# PCB0M8B3.net
KiCad netlist of a schematic drawn in EAGLE
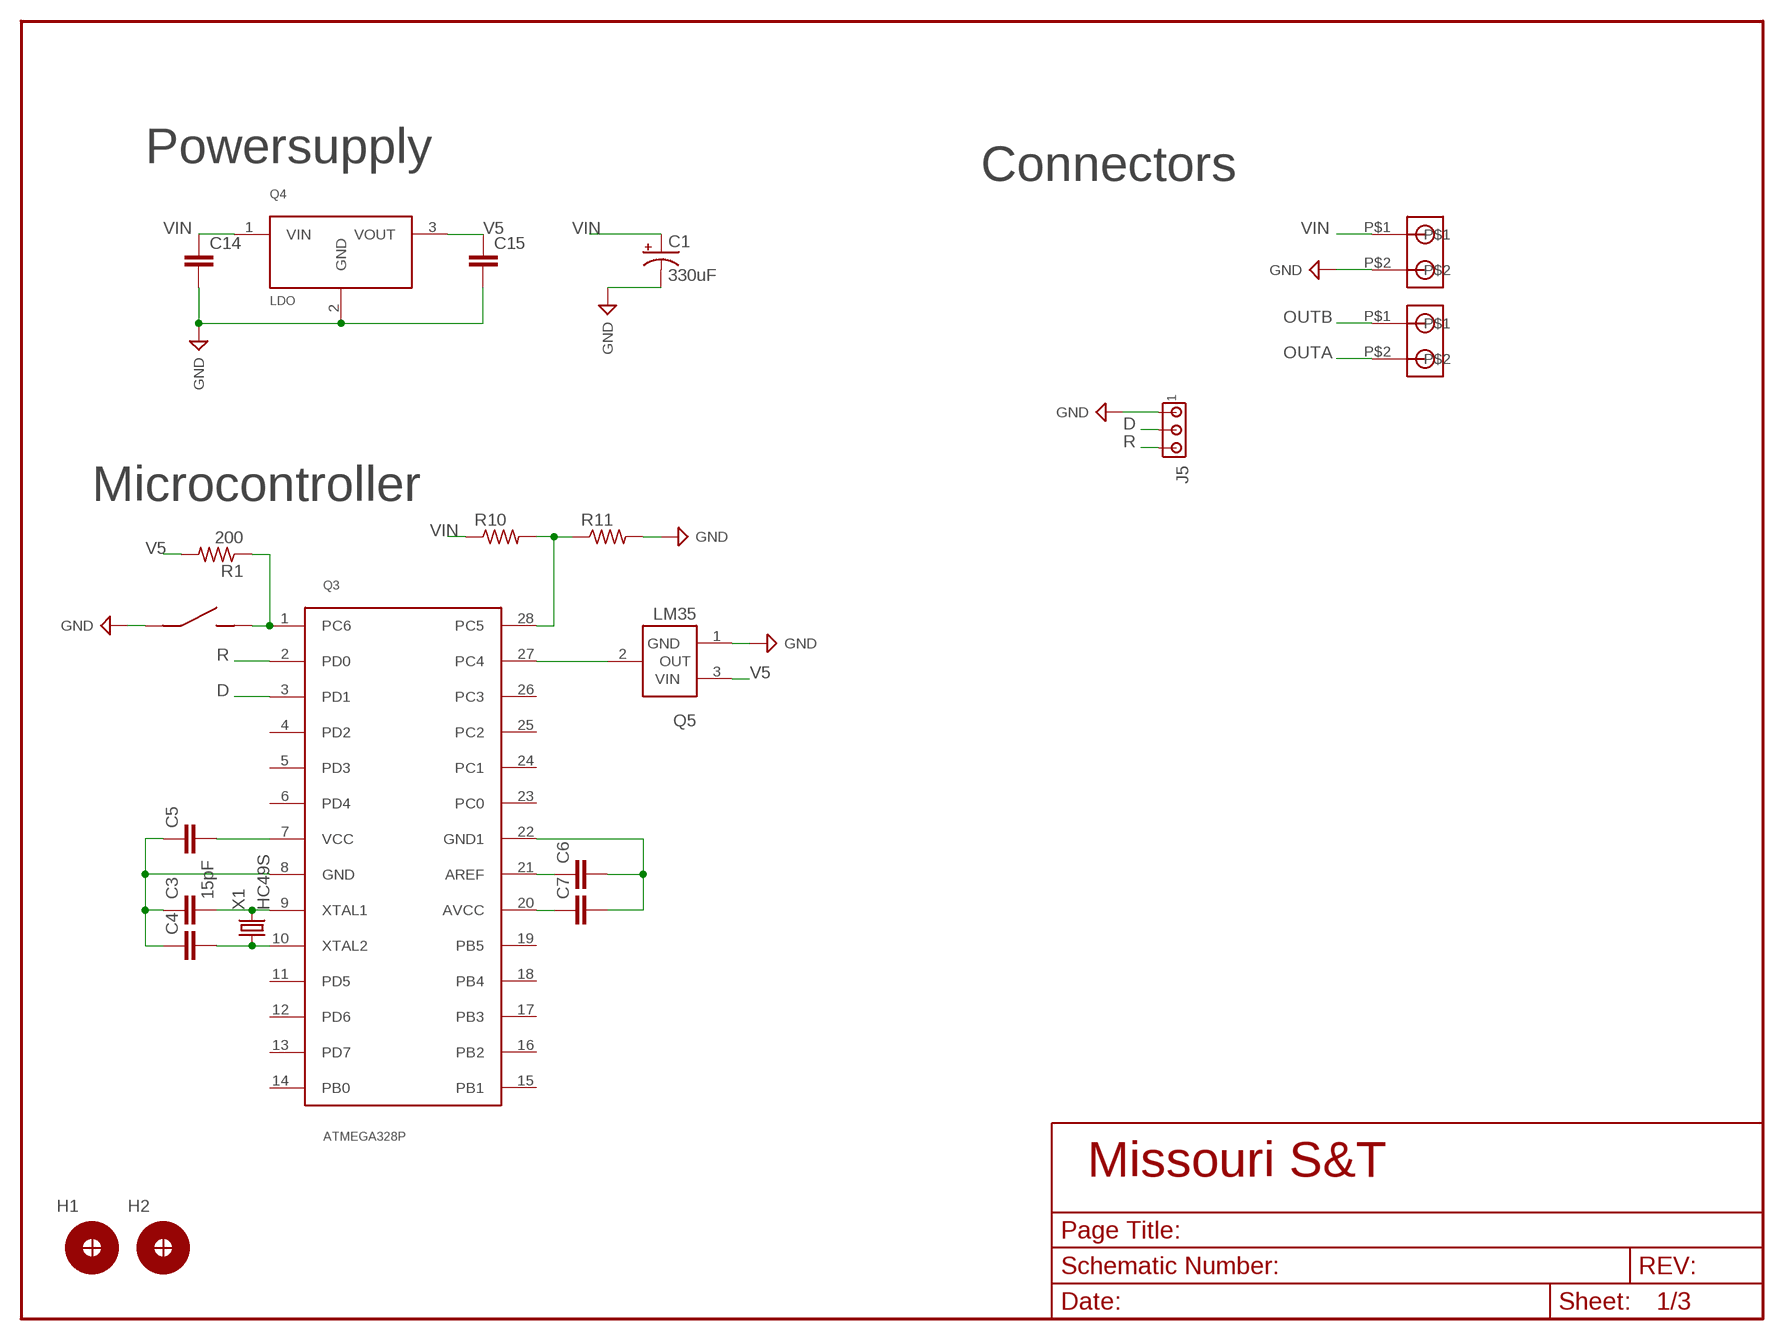
[diagram p0: schematic, sheet 1]
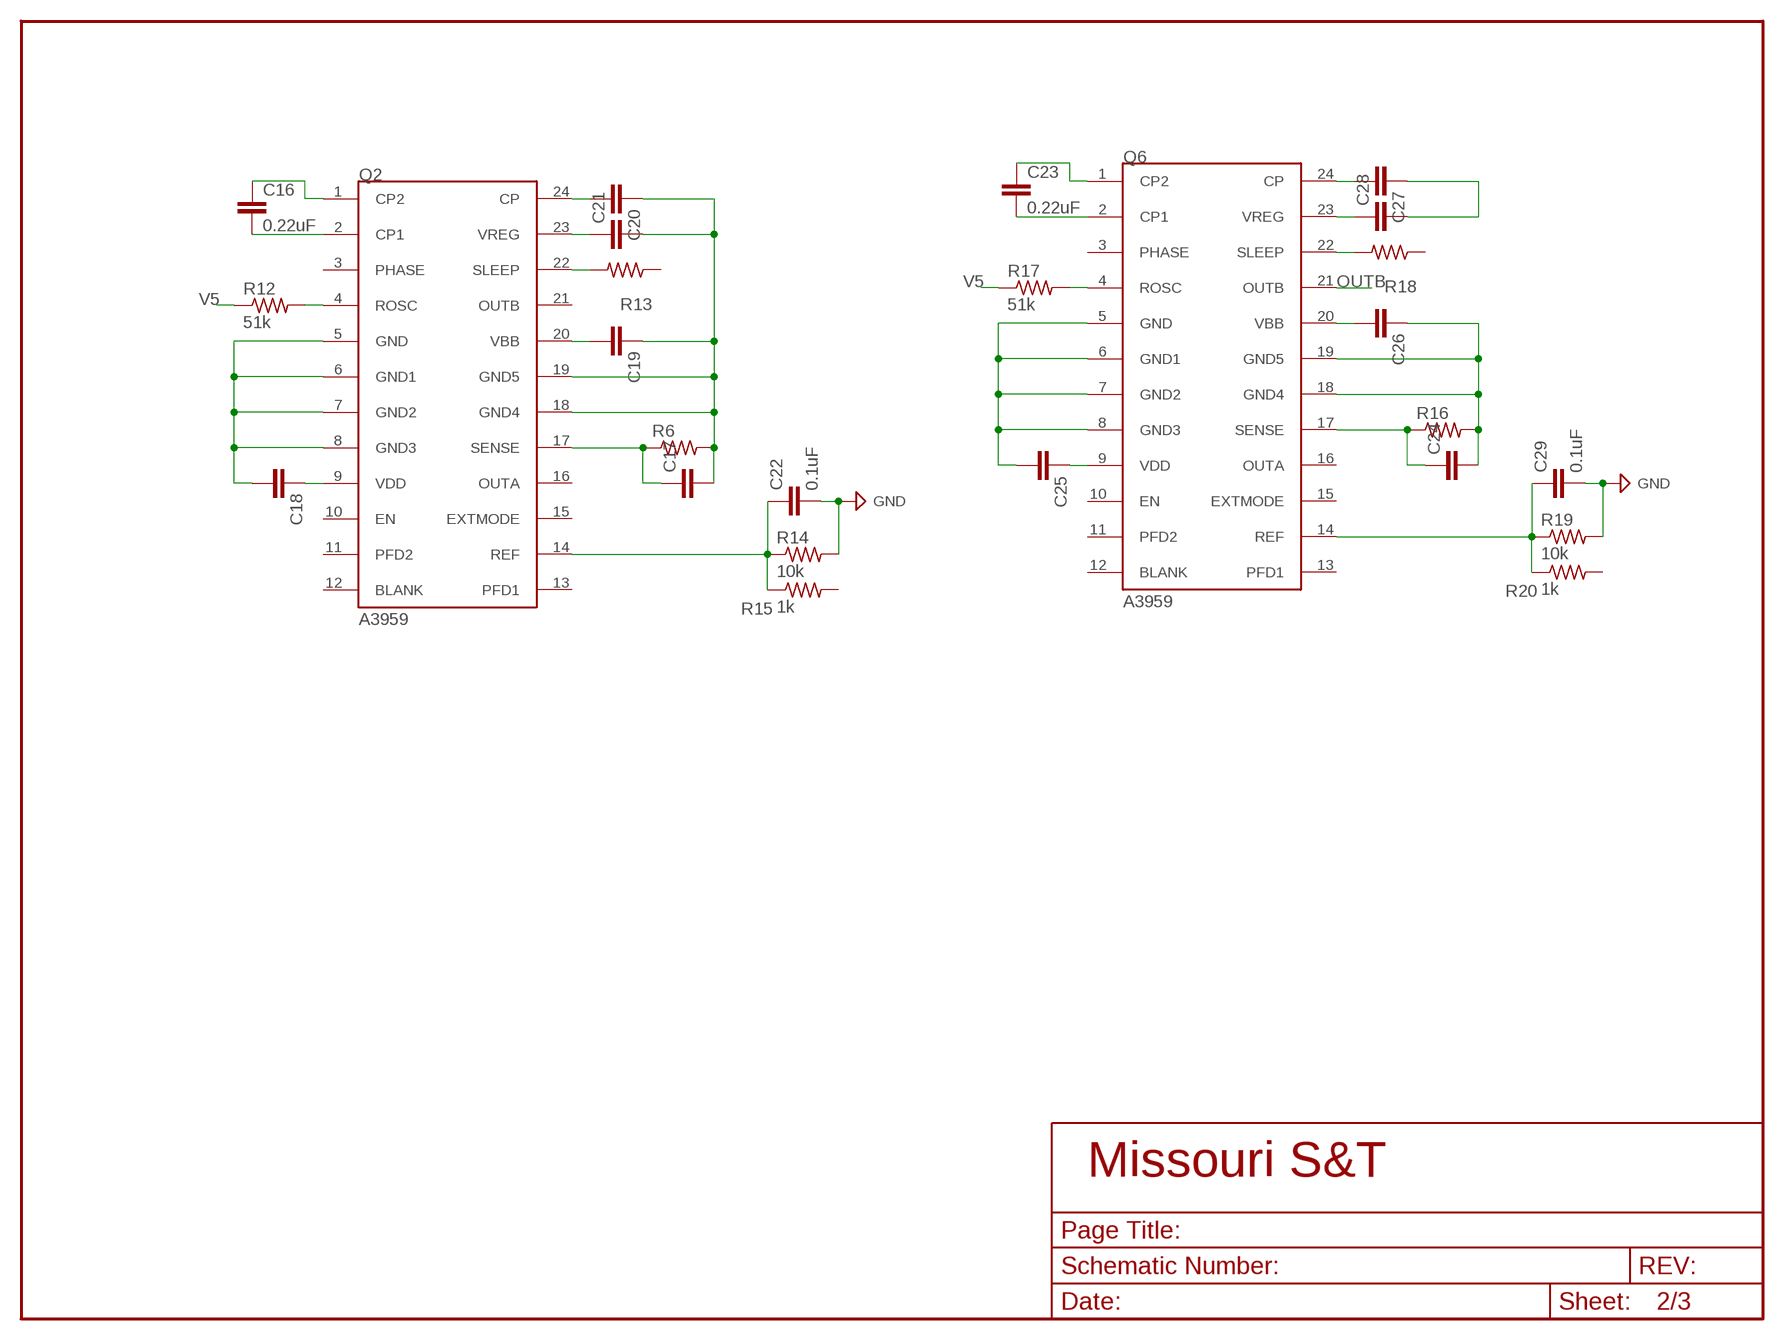
[diagram p1: schematic, sheet 2]
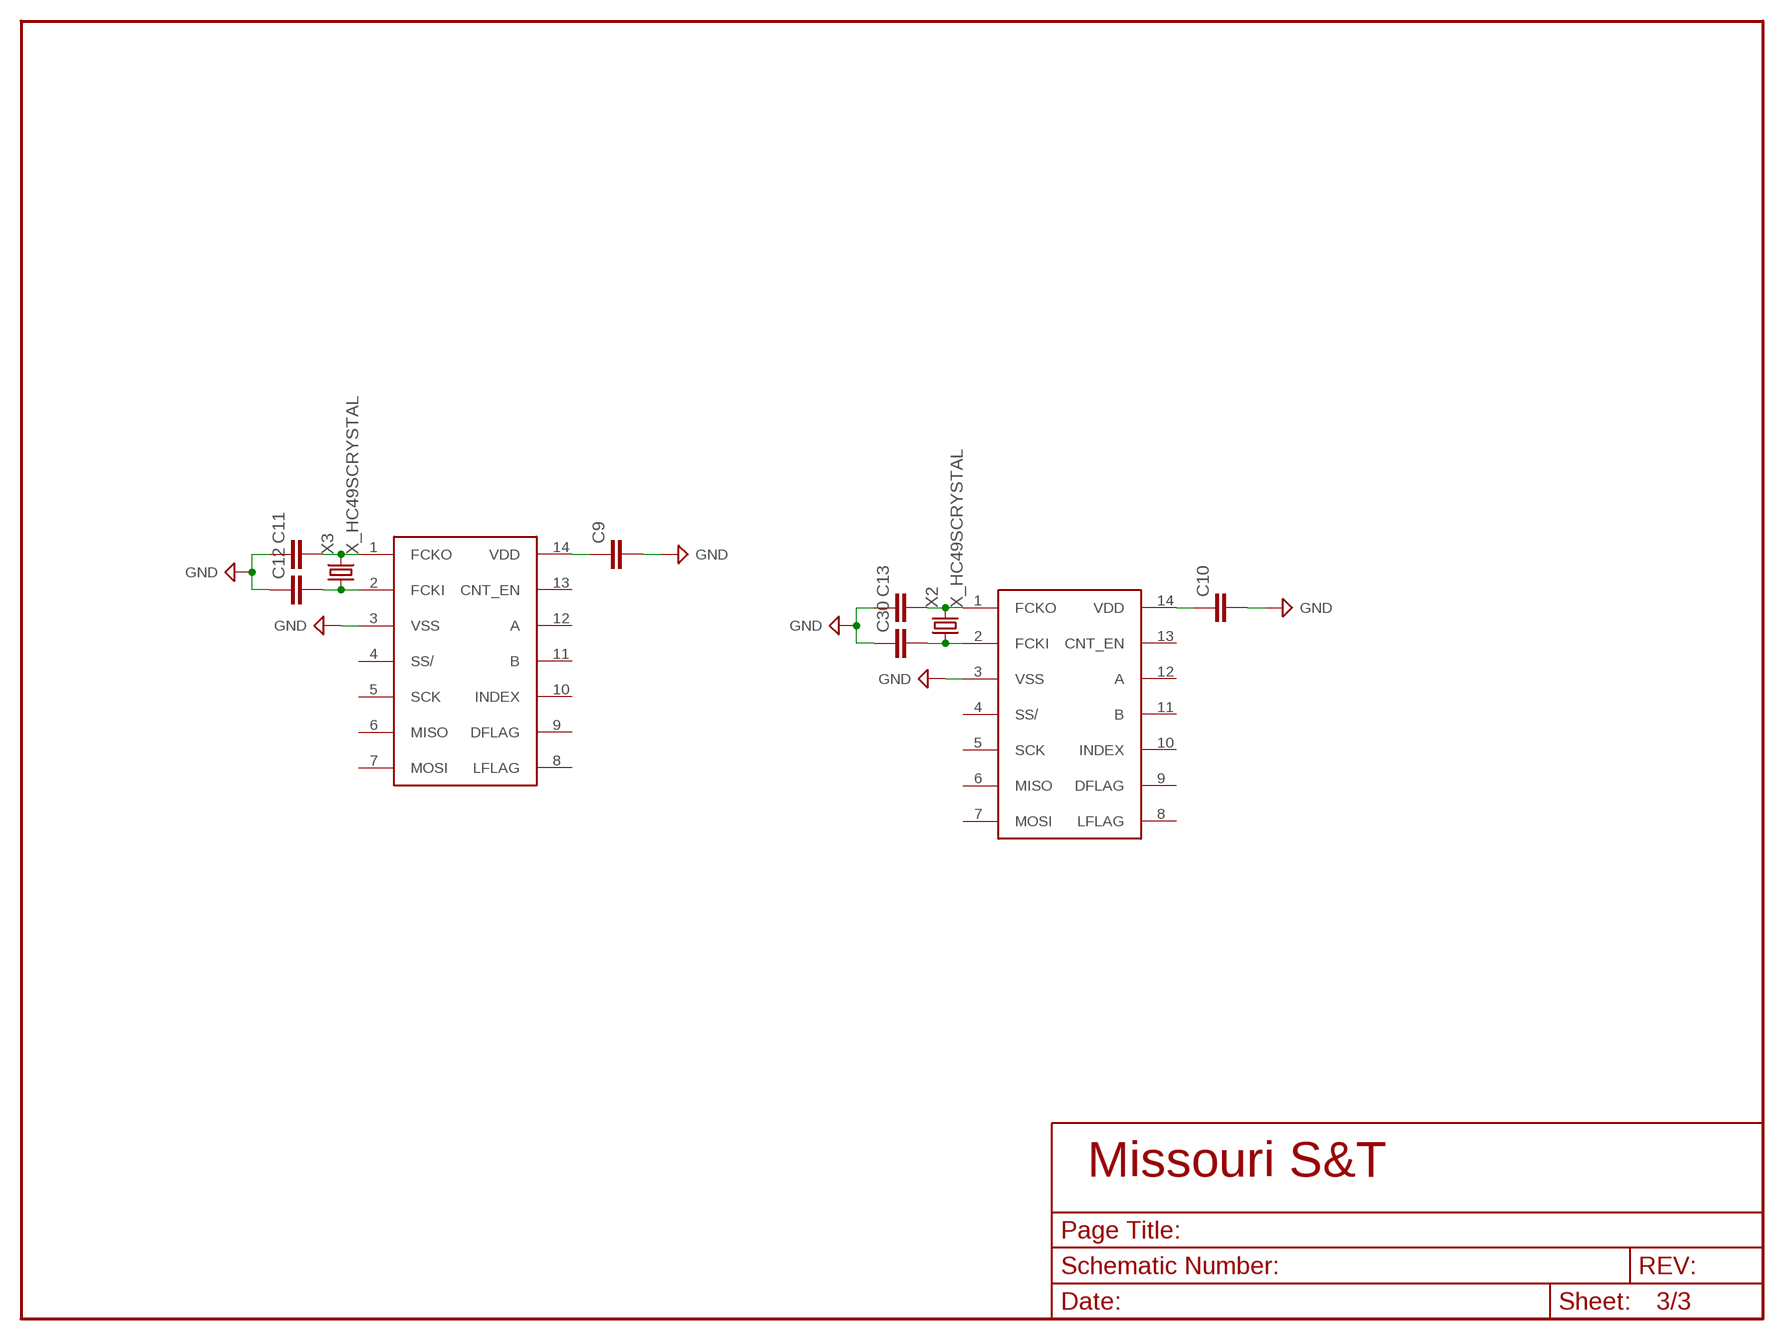
[diagram p2: schematic, sheet 3]

(export (version "E")
  (design (tool "Eeschema 10.0.6"))
  (components
    (comp (ref "C9")
      (value "C_CAP_1206")
      (footprint "eagle-import:C_1206")
      (libsource (lib "eagle-import") (part "C_CAP_1206"))
    )
    (comp (ref "C10")
      (value "C_CAP_0805")
      (footprint "eagle-import:C_0805")
      (libsource (lib "eagle-import") (part "C_CAP_0805"))
    )
    (comp (ref "C11")
      (value "C_CAP_0805")
      (footprint "eagle-import:C_0805")
      (libsource (lib "eagle-import") (part "C_CAP_0805"))
    )
    (comp (ref "C12")
      (value "C_CAP_0805")
      (footprint "eagle-import:C_0805")
      (libsource (lib "eagle-import") (part "C_CAP_0805"))
    )
    (comp (ref "C13")
      (value "C_CAP_0805")
      (footprint "eagle-import:C_0805")
      (libsource (lib "eagle-import") (part "C_CAP_0805"))
    )
    (comp (ref "C30")
      (value "C_CAP_0805")
      (footprint "eagle-import:C_0805")
      (libsource (lib "eagle-import") (part "C_CAP_0805"))
    )
    (comp (ref "Q8")
      (value "Q_LFLS7366R-S")
      (footprint "eagle-import:SOIC14")
      (libsource (lib "eagle-import") (part "Q_LFLS7366R-S"))
    )
    (comp (ref "Q9")
      (value "Q_LFLS7366R-S")
      (footprint "eagle-import:SOIC14")
      (libsource (lib "eagle-import") (part "Q_LFLS7366R-S"))
    )
    (comp (ref "X2")
      (value "X_HC49SCRYSTAL")
      (footprint "eagle-import:HC-49")
      (libsource (lib "eagle-import") (part "X_HC49SCRYSTAL"))
    )
    (comp (ref "X3")
      (value "X_HC49SCRYSTAL")
      (footprint "eagle-import:HC-49")
      (libsource (lib "eagle-import") (part "X_HC49SCRYSTAL"))
    )
    (comp (ref "C1")
      (value "330uF")
      (footprint "eagle-import:C_8MM")
      (libsource (lib "eagle-import") (part "C_POL8MM"))
    )
    (comp (ref "C3")
      (value "15pF")
      (footprint "eagle-import:C_0805")
      (libsource (lib "eagle-import") (part "C_CAP_0805"))
    )
    (comp (ref "C4")
      (value "C_CAP_0805")
      (footprint "eagle-import:C_0805")
      (libsource (lib "eagle-import") (part "C_CAP_0805"))
    )
    (comp (ref "C5")
      (value "C_CAP_0805")
      (footprint "eagle-import:C_0805")
      (libsource (lib "eagle-import") (part "C_CAP_0805"))
    )
    (comp (ref "C6")
      (value "C_CAP_0805")
      (footprint "eagle-import:C_0805")
      (libsource (lib "eagle-import") (part "C_CAP_0805"))
    )
    (comp (ref "C7")
      (value "C_CAP_0805")
      (footprint "eagle-import:C_0805")
      (libsource (lib "eagle-import") (part "C_CAP_0805"))
    )
    (comp (ref "C14")
      (value "C_CAP_0805")
      (footprint "eagle-import:C_0805")
      (libsource (lib "eagle-import") (part "C_CAP_0805"))
    )
    (comp (ref "C15")
      (value "C_CAP_0805")
      (footprint "eagle-import:C_0805")
      (libsource (lib "eagle-import") (part "C_CAP_0805"))
    )
    (comp (ref "H1")
      (value "H_MNTHOLE_#4")
      (footprint "eagle-import:H_MNTHOLE_#4")
      (libsource (lib "eagle-import") (part "H_MNTHOLE_#4"))
    )
    (comp (ref "H2")
      (value "H_MNTHOLE_#4")
      (footprint "eagle-import:H_MNTHOLE_#4")
      (libsource (lib "eagle-import") (part "H_MNTHOLE_#4"))
    )
    (comp (ref "J1")
      (value "J_1546074-2282834-2")
      (footprint "eagle-import:J_2.54MM")
      (libsource (lib "eagle-import") (part "J_1546074-2282834-2"))
    )
    (comp (ref "J2")
      (value "J_1546074-2282834-2")
      (footprint "eagle-import:J_2.54MM")
      (libsource (lib "eagle-import") (part "J_1546074-2282834-2"))
    )
    (comp (ref "J4")
      (value "J_MC32857")
      (footprint "eagle-import:J_TOGGLE")
      (libsource (lib "eagle-import") (part "J_MC32857"))
    )
    (comp (ref "J5")
      (value "J_MTA3P_100")
      (footprint "eagle-import:J_MTA100_3P")
      (libsource (lib "eagle-import") (part "J_MTA3P_100"))
    )
    (comp (ref "Q3")
      (value "ATMEGA328P")
      (footprint "eagle-import:DIP28")
      (libsource (lib "eagle-import") (part "Q_ATMEGA328P"))
    )
    (comp (ref "Q4")
      (value "LDO")
      (footprint "eagle-import:TO-220")
      (libsource (lib "eagle-import") (part "Q_LDO"))
    )
    (comp (ref "Q5")
      (value "LM35")
      (footprint "eagle-import:TO-92-3")
      (libsource (lib "eagle-import") (part "Q_LM35"))
    )
    (comp (ref "R1")
      (value "200")
      (footprint "eagle-import:R_0805")
      (libsource (lib "eagle-import") (part "R_RES_0805"))
    )
    (comp (ref "R10")
      (value "R_RES_0805")
      (footprint "eagle-import:R_0805")
      (libsource (lib "eagle-import") (part "R_RES_0805"))
    )
    (comp (ref "R11")
      (value "R_RES_0805")
      (footprint "eagle-import:R_0805")
      (libsource (lib "eagle-import") (part "R_RES_0805"))
    )
    (comp (ref "X1")
      (value "HC49S")
      (footprint "eagle-import:HC-49")
      (libsource (lib "eagle-import") (part "X_HC49SCRYSTAL"))
    )
    (comp (ref "C16")
      (value "0.22uF")
      (footprint "eagle-import:C_0805")
      (libsource (lib "eagle-import") (part "C_CAP_0805"))
    )
    (comp (ref "C17")
      (value "C_CAP_0805")
      (footprint "eagle-import:C_0805")
      (libsource (lib "eagle-import") (part "C_CAP_0805"))
    )
    (comp (ref "C18")
      (value "C_CAP_0805")
      (footprint "eagle-import:C_0805")
      (libsource (lib "eagle-import") (part "C_CAP_0805"))
    )
    (comp (ref "C19")
      (value "C_CAP_0805")
      (footprint "eagle-import:C_0805")
      (libsource (lib "eagle-import") (part "C_CAP_0805"))
    )
    (comp (ref "C20")
      (value "C_CAP_0805")
      (footprint "eagle-import:C_0805")
      (libsource (lib "eagle-import") (part "C_CAP_0805"))
    )
    (comp (ref "C21")
      (value "C_CAP_0805")
      (footprint "eagle-import:C_0805")
      (libsource (lib "eagle-import") (part "C_CAP_0805"))
    )
    (comp (ref "C22")
      (value "0.1uF")
      (footprint "eagle-import:C_0805")
      (libsource (lib "eagle-import") (part "C_CAP_0805"))
    )
    (comp (ref "C23")
      (value "0.22uF")
      (footprint "eagle-import:C_0805")
      (libsource (lib "eagle-import") (part "C_CAP_0805"))
    )
    (comp (ref "C24")
      (value "C_CAP_0805")
      (footprint "eagle-import:C_0805")
      (libsource (lib "eagle-import") (part "C_CAP_0805"))
    )
    (comp (ref "C25")
      (value "C_CAP_0805")
      (footprint "eagle-import:C_0805")
      (libsource (lib "eagle-import") (part "C_CAP_0805"))
    )
    (comp (ref "C26")
      (value "C_CAP_0805")
      (footprint "eagle-import:C_0805")
      (libsource (lib "eagle-import") (part "C_CAP_0805"))
    )
    (comp (ref "C27")
      (value "C_CAP_0805")
      (footprint "eagle-import:C_0805")
      (libsource (lib "eagle-import") (part "C_CAP_0805"))
    )
    (comp (ref "C28")
      (value "C_CAP_0805")
      (footprint "eagle-import:C_0805")
      (libsource (lib "eagle-import") (part "C_CAP_0805"))
    )
    (comp (ref "C29")
      (value "0.1uF")
      (footprint "eagle-import:C_0805")
      (libsource (lib "eagle-import") (part "C_CAP_0805"))
    )
    (comp (ref "Q2")
      (value "A3959")
      (footprint "eagle-import:DIP24")
      (libsource (lib "eagle-import") (part "Q_A3959"))
    )
    (comp (ref "Q6")
      (value "A3959")
      (footprint "eagle-import:DIP24")
      (libsource (lib "eagle-import") (part "Q_A3959"))
    )
    (comp (ref "R6")
      (value "R_RES_2010")
      (footprint "eagle-import:R_2010")
      (libsource (lib "eagle-import") (part "R_RES_2010"))
    )
    (comp (ref "R12")
      (value "51k")
      (footprint "eagle-import:R_0805")
      (libsource (lib "eagle-import") (part "R_RES_0805"))
    )
    (comp (ref "R13")
      (value "R_1/4WL")
      (footprint "eagle-import:R_1_4WL")
      (libsource (lib "eagle-import") (part "R_1/4WL"))
    )
    (comp (ref "R14")
      (value "10k")
      (footprint "eagle-import:R_0805")
      (libsource (lib "eagle-import") (part "R_RES_0805"))
    )
    (comp (ref "R15")
      (value "1k")
      (footprint "eagle-import:R_0805")
      (libsource (lib "eagle-import") (part "R_RES_0805"))
    )
    (comp (ref "R16")
      (value "R_RES_2010")
      (footprint "eagle-import:R_2010")
      (libsource (lib "eagle-import") (part "R_RES_2010"))
    )
    (comp (ref "R17")
      (value "51k")
      (footprint "eagle-import:R_0805")
      (libsource (lib "eagle-import") (part "R_RES_0805"))
    )
    (comp (ref "R18")
      (value "R_1/4WL")
      (footprint "eagle-import:R_1_4WL")
      (libsource (lib "eagle-import") (part "R_1/4WL"))
    )
    (comp (ref "R19")
      (value "10k")
      (footprint "eagle-import:R_0805")
      (libsource (lib "eagle-import") (part "R_RES_0805"))
    )
    (comp (ref "R20")
      (value "1k")
      (footprint "eagle-import:R_0805")
      (libsource (lib "eagle-import") (part "R_RES_0805"))
    )
  )
  (nets
    (net (code "1") (name "D") (class "Default")
      (node (ref "J5") (pin "2") (pinfunction "2_2") (pintype "passive"))
      (node (ref "Q3") (pin "3") (pinfunction "PD1_3") (pintype "bidirectional"))
    )
    (net (code "2") (name "GND") (class "Default")
      (node (ref "C1") (pin "-") (pinfunction "-_-") (pintype "passive"))
      (node (ref "C10") (pin "2") (pinfunction "2_2") (pintype "passive"))
      (node (ref "C11") (pin "1") (pinfunction "1_1") (pintype "passive"))
      (node (ref "C12") (pin "1") (pinfunction "1_1") (pintype "passive"))
      (node (ref "C13") (pin "1") (pinfunction "1_1") (pintype "passive"))
      (node (ref "C14") (pin "2") (pinfunction "2_2") (pintype "passive"))
      (node (ref "C15") (pin "2") (pinfunction "2_2") (pintype "passive"))
      (node (ref "C17") (pin "2") (pinfunction "2_2") (pintype "passive"))
      (node (ref "C18") (pin "2") (pinfunction "2_2") (pintype "passive"))
      (node (ref "C19") (pin "1") (pinfunction "1_1") (pintype "passive"))
      (node (ref "C20") (pin "1") (pinfunction "1_1") (pintype "passive"))
      (node (ref "C21") (pin "2") (pinfunction "2_2") (pintype "passive"))
      (node (ref "C22") (pin "2") (pinfunction "2_2") (pintype "passive"))
      (node (ref "C24") (pin "2") (pinfunction "2_2") (pintype "passive"))
      (node (ref "C25") (pin "2") (pinfunction "2_2") (pintype "passive"))
      (node (ref "C26") (pin "1") (pinfunction "1_1") (pintype "passive"))
      (node (ref "C29") (pin "2") (pinfunction "2_2") (pintype "passive"))
      (node (ref "C3") (pin "1") (pinfunction "1_1") (pintype "passive"))
      (node (ref "C30") (pin "1") (pinfunction "1_1") (pintype "passive"))
      (node (ref "C4") (pin "1") (pinfunction "1_1") (pintype "passive"))
      (node (ref "C5") (pin "1") (pinfunction "1_1") (pintype "passive"))
      (node (ref "C6") (pin "2") (pinfunction "2_2") (pintype "passive"))
      (node (ref "C7") (pin "2") (pinfunction "2_2") (pintype "passive"))
      (node (ref "C9") (pin "2") (pinfunction "2_2") (pintype "passive"))
      (node (ref "J1") (pin "P$2") (pinfunction "P$2_P$2") (pintype "bidirectional"))
      (node (ref "J4") (pin "P$1") (pinfunction "1_P$1") (pintype "bidirectional"))
      (node (ref "J5") (pin "1") (pinfunction "1_1") (pintype "passive"))
      (node (ref "Q2") (pin "18") (pinfunction "GND4_18") (pintype "bidirectional"))
      (node (ref "Q2") (pin "19") (pinfunction "GND5_19") (pintype "bidirectional"))
      (node (ref "Q2") (pin "5") (pinfunction "GND_5") (pintype "bidirectional"))
      (node (ref "Q2") (pin "6") (pinfunction "GND1_6") (pintype "bidirectional"))
      (node (ref "Q2") (pin "7") (pinfunction "GND2_7") (pintype "bidirectional"))
      (node (ref "Q2") (pin "8") (pinfunction "GND3_8") (pintype "bidirectional"))
      (node (ref "Q3") (pin "22") (pinfunction "GND1_22") (pintype "bidirectional"))
      (node (ref "Q3") (pin "8") (pinfunction "GND_8") (pintype "bidirectional"))
      (node (ref "Q4") (pin "2") (pinfunction "GND_2") (pintype "bidirectional"))
      (node (ref "Q5") (pin "1") (pinfunction "GND_1") (pintype "bidirectional"))
      (node (ref "Q6") (pin "18") (pinfunction "GND4_18") (pintype "bidirectional"))
      (node (ref "Q6") (pin "19") (pinfunction "GND5_19") (pintype "bidirectional"))
      (node (ref "Q6") (pin "5") (pinfunction "GND_5") (pintype "bidirectional"))
      (node (ref "Q6") (pin "6") (pinfunction "GND1_6") (pintype "bidirectional"))
      (node (ref "Q6") (pin "7") (pinfunction "GND2_7") (pintype "bidirectional"))
      (node (ref "Q6") (pin "8") (pinfunction "GND3_8") (pintype "bidirectional"))
      (node (ref "Q8") (pin "3") (pinfunction "VSS_3") (pintype "bidirectional"))
      (node (ref "Q9") (pin "3") (pinfunction "VSS_3") (pintype "bidirectional"))
      (node (ref "R11") (pin "2") (pinfunction "2_2") (pintype "passive"))
      (node (ref "R14") (pin "2") (pinfunction "2_2") (pintype "passive"))
      (node (ref "R16") (pin "2") (pinfunction "2_2") (pintype "passive"))
      (node (ref "R19") (pin "2") (pinfunction "2_2") (pintype "passive"))
      (node (ref "R6") (pin "2") (pinfunction "2_2") (pintype "passive"))
    )
    (net (code "3") (name "ISENSE") (class "Default")
      (node (ref "C17") (pin "1") (pinfunction "1_1") (pintype "passive"))
      (node (ref "C24") (pin "1") (pinfunction "1_1") (pintype "passive"))
      (node (ref "Q2") (pin "17") (pinfunction "SENSE_17") (pintype "bidirectional"))
      (node (ref "Q6") (pin "17") (pinfunction "SENSE_17") (pintype "bidirectional"))
      (node (ref "R16") (pin "1") (pinfunction "1_1") (pintype "passive"))
      (node (ref "R6") (pin "1") (pinfunction "1_1") (pintype "passive"))
    )
    (net (code "4") (name "Net-(C27-Pad1)") (class "Default")
      (node (ref "C27") (pin "1") (pinfunction "1_1") (pintype "passive"))
      (node (ref "C28") (pin "2") (pinfunction "2_2") (pintype "passive"))
    )
    (net (code "5") (name "Net-(J4-2)") (class "Default")
      (node (ref "J4") (pin "P$2") (pinfunction "2_P$2") (pintype "bidirectional"))
      (node (ref "Q3") (pin "1") (pinfunction "PC6_1") (pintype "bidirectional"))
      (node (ref "R1") (pin "1") (pinfunction "1_1") (pintype "passive"))
    )
    (net (code "6") (name "Net-(Q2-CP)") (class "Default")
      (node (ref "C20") (pin "2") (pinfunction "2_2") (pintype "passive"))
      (node (ref "Q2") (pin "24") (pinfunction "CP_24") (pintype "bidirectional"))
    )
    (net (code "7") (name "Net-(Q2-CP1)") (class "Default")
      (node (ref "C16") (pin "2") (pinfunction "2_2") (pintype "passive"))
      (node (ref "Q2") (pin "2") (pinfunction "CP1_2") (pintype "bidirectional"))
    )
    (net (code "8") (name "Net-(Q2-CP2)") (class "Default")
      (node (ref "C16") (pin "1") (pinfunction "1_1") (pintype "passive"))
      (node (ref "Q2") (pin "1") (pinfunction "CP2_1") (pintype "bidirectional"))
    )
    (net (code "9") (name "Net-(Q2-REF)") (class "Default")
      (node (ref "C22") (pin "1") (pinfunction "1_1") (pintype "passive"))
      (node (ref "Q2") (pin "14") (pinfunction "REF_14") (pintype "bidirectional"))
      (node (ref "R14") (pin "1") (pinfunction "1_1") (pintype "passive"))
      (node (ref "R15") (pin "1") (pinfunction "1_1") (pintype "passive"))
    )
    (net (code "10") (name "Net-(Q2-ROSC)") (class "Default")
      (node (ref "Q2") (pin "4") (pinfunction "ROSC_4") (pintype "bidirectional"))
      (node (ref "R12") (pin "2") (pinfunction "2_2") (pintype "passive"))
    )
    (net (code "11") (name "Net-(Q2-SLEEP)") (class "Default")
      (node (ref "Q2") (pin "22") (pinfunction "SLEEP_22") (pintype "bidirectional"))
      (node (ref "R13") (pin "2") (pinfunction "2_2") (pintype "passive"))
    )
    (net (code "12") (name "Net-(Q2-VREG)") (class "Default")
      (node (ref "C21") (pin "1") (pinfunction "1_1") (pintype "passive"))
      (node (ref "Q2") (pin "23") (pinfunction "VREG_23") (pintype "bidirectional"))
    )
    (net (code "13") (name "Net-(Q3-AREF)") (class "Default")
      (node (ref "C6") (pin "1") (pinfunction "1_1") (pintype "passive"))
      (node (ref "Q3") (pin "21") (pinfunction "AREF_21") (pintype "bidirectional"))
    )
    (net (code "14") (name "Net-(Q3-PC4)") (class "Default")
      (node (ref "Q3") (pin "27") (pinfunction "PC4_27") (pintype "bidirectional"))
      (node (ref "Q5") (pin "2") (pinfunction "OUT_2") (pintype "bidirectional"))
    )
    (net (code "15") (name "Net-(Q3-PC5)") (class "Default")
      (node (ref "Q3") (pin "28") (pinfunction "PC5_28") (pintype "bidirectional"))
      (node (ref "R10") (pin "2") (pinfunction "2_2") (pintype "passive"))
      (node (ref "R11") (pin "1") (pinfunction "1_1") (pintype "passive"))
    )
    (net (code "16") (name "Net-(Q3-XTAL1)") (class "Default")
      (node (ref "C3") (pin "2") (pinfunction "2_2") (pintype "passive"))
      (node (ref "Q3") (pin "9") (pinfunction "XTAL1_9") (pintype "bidirectional"))
      (node (ref "X1") (pin "P$2") (pinfunction "2_P$2") (pintype "passive"))
    )
    (net (code "17") (name "Net-(Q3-XTAL2)") (class "Default")
      (node (ref "C4") (pin "2") (pinfunction "2_2") (pintype "passive"))
      (node (ref "Q3") (pin "10") (pinfunction "XTAL2_10") (pintype "bidirectional"))
      (node (ref "X1") (pin "P$1") (pinfunction "1_P$1") (pintype "passive"))
    )
    (net (code "18") (name "Net-(Q6-CP)") (class "Default")
      (node (ref "C27") (pin "2") (pinfunction "2_2") (pintype "passive"))
      (node (ref "Q6") (pin "24") (pinfunction "CP_24") (pintype "bidirectional"))
    )
    (net (code "19") (name "Net-(Q6-CP1)") (class "Default")
      (node (ref "C23") (pin "2") (pinfunction "2_2") (pintype "passive"))
      (node (ref "Q6") (pin "2") (pinfunction "CP1_2") (pintype "bidirectional"))
    )
    (net (code "20") (name "Net-(Q6-CP2)") (class "Default")
      (node (ref "C23") (pin "1") (pinfunction "1_1") (pintype "passive"))
      (node (ref "Q6") (pin "1") (pinfunction "CP2_1") (pintype "bidirectional"))
    )
    (net (code "21") (name "Net-(Q6-REF)") (class "Default")
      (node (ref "C29") (pin "1") (pinfunction "1_1") (pintype "passive"))
      (node (ref "Q6") (pin "14") (pinfunction "REF_14") (pintype "bidirectional"))
      (node (ref "R19") (pin "1") (pinfunction "1_1") (pintype "passive"))
      (node (ref "R20") (pin "1") (pinfunction "1_1") (pintype "passive"))
    )
    (net (code "22") (name "Net-(Q6-ROSC)") (class "Default")
      (node (ref "Q6") (pin "4") (pinfunction "ROSC_4") (pintype "bidirectional"))
      (node (ref "R17") (pin "2") (pinfunction "2_2") (pintype "passive"))
    )
    (net (code "23") (name "Net-(Q6-SLEEP)") (class "Default")
      (node (ref "Q6") (pin "22") (pinfunction "SLEEP_22") (pintype "bidirectional"))
      (node (ref "R18") (pin "2") (pinfunction "2_2") (pintype "passive"))
    )
    (net (code "24") (name "Net-(Q6-VREG)") (class "Default")
      (node (ref "C28") (pin "1") (pinfunction "1_1") (pintype "passive"))
      (node (ref "Q6") (pin "23") (pinfunction "VREG_23") (pintype "bidirectional"))
    )
    (net (code "25") (name "Net-(Q8-FCKI)") (class "Default")
      (node (ref "C12") (pin "2") (pinfunction "2_2") (pintype "passive"))
      (node (ref "Q8") (pin "2") (pinfunction "FCKI_2") (pintype "bidirectional"))
      (node (ref "X3") (pin "P$1") (pinfunction "1_P$1") (pintype "passive"))
    )
    (net (code "26") (name "Net-(Q8-FCKO)") (class "Default")
      (node (ref "C11") (pin "2") (pinfunction "2_2") (pintype "passive"))
      (node (ref "Q8") (pin "1") (pinfunction "FCKO_1") (pintype "bidirectional"))
      (node (ref "X3") (pin "P$2") (pinfunction "2_P$2") (pintype "passive"))
    )
    (net (code "27") (name "Net-(Q8-VDD)") (class "Default")
      (node (ref "C9") (pin "1") (pinfunction "1_1") (pintype "passive"))
      (node (ref "Q8") (pin "14") (pinfunction "VDD_14") (pintype "bidirectional"))
    )
    (net (code "28") (name "Net-(Q9-FCKI)") (class "Default")
      (node (ref "C30") (pin "2") (pinfunction "2_2") (pintype "passive"))
      (node (ref "Q9") (pin "2") (pinfunction "FCKI_2") (pintype "bidirectional"))
      (node (ref "X2") (pin "P$1") (pinfunction "1_P$1") (pintype "passive"))
    )
    (net (code "29") (name "Net-(Q9-FCKO)") (class "Default")
      (node (ref "C13") (pin "2") (pinfunction "2_2") (pintype "passive"))
      (node (ref "Q9") (pin "1") (pinfunction "FCKO_1") (pintype "bidirectional"))
      (node (ref "X2") (pin "P$2") (pinfunction "2_P$2") (pintype "passive"))
    )
    (net (code "30") (name "Net-(Q9-VDD)") (class "Default")
      (node (ref "C10") (pin "1") (pinfunction "1_1") (pintype "passive"))
      (node (ref "Q9") (pin "14") (pinfunction "VDD_14") (pintype "bidirectional"))
    )
    (net (code "31") (name "OUTA") (class "Default")
      (node (ref "J2") (pin "P$2") (pinfunction "P$2_P$2") (pintype "bidirectional"))
    )
    (net (code "32") (name "OUTB") (class "Default")
      (node (ref "J2") (pin "P$1") (pinfunction "P$1_P$1") (pintype "bidirectional"))
      (node (ref "Q6") (pin "21") (pinfunction "OUTB_21") (pintype "bidirectional"))
    )
    (net (code "33") (name "R") (class "Default")
      (node (ref "J5") (pin "3") (pinfunction "3_3") (pintype "passive"))
      (node (ref "Q3") (pin "2") (pinfunction "PD0_2") (pintype "bidirectional"))
    )
    (net (code "34") (name "V5") (class "Default")
      (node (ref "C15") (pin "1") (pinfunction "1_1") (pintype "passive"))
      (node (ref "C18") (pin "1") (pinfunction "1_1") (pintype "passive"))
      (node (ref "C25") (pin "1") (pinfunction "1_1") (pintype "passive"))
      (node (ref "C5") (pin "2") (pinfunction "2_2") (pintype "passive"))
      (node (ref "C7") (pin "1") (pinfunction "1_1") (pintype "passive"))
      (node (ref "Q2") (pin "9") (pinfunction "VDD_9") (pintype "bidirectional"))
      (node (ref "Q3") (pin "20") (pinfunction "AVCC_20") (pintype "bidirectional"))
      (node (ref "Q3") (pin "7") (pinfunction "VCC_7") (pintype "bidirectional"))
      (node (ref "Q4") (pin "3") (pinfunction "VOUT_3") (pintype "bidirectional"))
      (node (ref "Q5") (pin "3") (pinfunction "VIN_3") (pintype "bidirectional"))
      (node (ref "Q6") (pin "9") (pinfunction "VDD_9") (pintype "bidirectional"))
      (node (ref "R1") (pin "2") (pinfunction "2_2") (pintype "passive"))
      (node (ref "R12") (pin "1") (pinfunction "1_1") (pintype "passive"))
      (node (ref "R17") (pin "1") (pinfunction "1_1") (pintype "passive"))
    )
    (net (code "35") (name "VIN") (class "Default")
      (node (ref "C1") (pin "+") (pinfunction "+_+") (pintype "passive"))
      (node (ref "C14") (pin "1") (pinfunction "1_1") (pintype "passive"))
      (node (ref "C19") (pin "2") (pinfunction "2_2") (pintype "passive"))
      (node (ref "C26") (pin "2") (pinfunction "2_2") (pintype "passive"))
      (node (ref "J1") (pin "P$1") (pinfunction "P$1_P$1") (pintype "bidirectional"))
      (node (ref "Q2") (pin "20") (pinfunction "VBB_20") (pintype "bidirectional"))
      (node (ref "Q4") (pin "1") (pinfunction "VIN_1") (pintype "bidirectional"))
      (node (ref "Q6") (pin "20") (pinfunction "VBB_20") (pintype "bidirectional"))
      (node (ref "R10") (pin "1") (pinfunction "1_1") (pintype "passive"))
    )
    (net (code "36") (name "unconnected-(H1-Pad1)") (class "Default")
      (node (ref "H1") (pin "1") (pinfunction "1_1") (pintype "passive"))
    )
    (net (code "37") (name "unconnected-(H2-Pad1)") (class "Default")
      (node (ref "H2") (pin "1") (pinfunction "1_1") (pintype "passive"))
    )
    (net (code "38") (name "unconnected-(Q2-BLANK-Pad12)") (class "Default")
      (node (ref "Q2") (pin "12") (pinfunction "BLANK_12") (pintype "bidirectional"))
    )
    (net (code "39") (name "unconnected-(Q2-EN-Pad10)") (class "Default")
      (node (ref "Q2") (pin "10") (pinfunction "EN_10") (pintype "bidirectional"))
    )
    (net (code "40") (name "unconnected-(Q2-EXTMODE-Pad15)") (class "Default")
      (node (ref "Q2") (pin "15") (pinfunction "EXTMODE_15") (pintype "bidirectional"))
    )
    (net (code "41") (name "unconnected-(Q2-OUTA-Pad16)") (class "Default")
      (node (ref "Q2") (pin "16") (pinfunction "OUTA_16") (pintype "bidirectional"))
    )
    (net (code "42") (name "unconnected-(Q2-OUTB-Pad21)") (class "Default")
      (node (ref "Q2") (pin "21") (pinfunction "OUTB_21") (pintype "bidirectional"))
    )
    (net (code "43") (name "unconnected-(Q2-PFD1-Pad13)") (class "Default")
      (node (ref "Q2") (pin "13") (pinfunction "PFD1_13") (pintype "bidirectional"))
    )
    (net (code "44") (name "unconnected-(Q2-PFD2-Pad11)") (class "Default")
      (node (ref "Q2") (pin "11") (pinfunction "PFD2_11") (pintype "bidirectional"))
    )
    (net (code "45") (name "unconnected-(Q2-PHASE-Pad3)") (class "Default")
      (node (ref "Q2") (pin "3") (pinfunction "PHASE_3") (pintype "bidirectional"))
    )
    (net (code "46") (name "unconnected-(Q3-PB0-Pad14)") (class "Default")
      (node (ref "Q3") (pin "14") (pinfunction "PB0_14") (pintype "bidirectional"))
    )
    (net (code "47") (name "unconnected-(Q3-PB1-Pad15)") (class "Default")
      (node (ref "Q3") (pin "15") (pinfunction "PB1_15") (pintype "bidirectional"))
    )
    (net (code "48") (name "unconnected-(Q3-PB2-Pad16)") (class "Default")
      (node (ref "Q3") (pin "16") (pinfunction "PB2_16") (pintype "bidirectional"))
    )
    (net (code "49") (name "unconnected-(Q3-PB3-Pad17)") (class "Default")
      (node (ref "Q3") (pin "17") (pinfunction "PB3_17") (pintype "bidirectional"))
    )
    (net (code "50") (name "unconnected-(Q3-PB4-Pad18)") (class "Default")
      (node (ref "Q3") (pin "18") (pinfunction "PB4_18") (pintype "bidirectional"))
    )
    (net (code "51") (name "unconnected-(Q3-PB5-Pad19)") (class "Default")
      (node (ref "Q3") (pin "19") (pinfunction "PB5_19") (pintype "bidirectional"))
    )
    (net (code "52") (name "unconnected-(Q3-PC0-Pad23)") (class "Default")
      (node (ref "Q3") (pin "23") (pinfunction "PC0_23") (pintype "bidirectional"))
    )
    (net (code "53") (name "unconnected-(Q3-PC1-Pad24)") (class "Default")
      (node (ref "Q3") (pin "24") (pinfunction "PC1_24") (pintype "bidirectional"))
    )
    (net (code "54") (name "unconnected-(Q3-PC2-Pad25)") (class "Default")
      (node (ref "Q3") (pin "25") (pinfunction "PC2_25") (pintype "bidirectional"))
    )
    (net (code "55") (name "unconnected-(Q3-PC3-Pad26)") (class "Default")
      (node (ref "Q3") (pin "26") (pinfunction "PC3_26") (pintype "bidirectional"))
    )
    (net (code "56") (name "unconnected-(Q3-PD2-Pad4)") (class "Default")
      (node (ref "Q3") (pin "4") (pinfunction "PD2_4") (pintype "bidirectional"))
    )
    (net (code "57") (name "unconnected-(Q3-PD3-Pad5)") (class "Default")
      (node (ref "Q3") (pin "5") (pinfunction "PD3_5") (pintype "bidirectional"))
    )
    (net (code "58") (name "unconnected-(Q3-PD4-Pad6)") (class "Default")
      (node (ref "Q3") (pin "6") (pinfunction "PD4_6") (pintype "bidirectional"))
    )
    (net (code "59") (name "unconnected-(Q3-PD5-Pad11)") (class "Default")
      (node (ref "Q3") (pin "11") (pinfunction "PD5_11") (pintype "bidirectional"))
    )
    (net (code "60") (name "unconnected-(Q3-PD6-Pad12)") (class "Default")
      (node (ref "Q3") (pin "12") (pinfunction "PD6_12") (pintype "bidirectional"))
    )
    (net (code "61") (name "unconnected-(Q3-PD7-Pad13)") (class "Default")
      (node (ref "Q3") (pin "13") (pinfunction "PD7_13") (pintype "bidirectional"))
    )
    (net (code "62") (name "unconnected-(Q6-BLANK-Pad12)") (class "Default")
      (node (ref "Q6") (pin "12") (pinfunction "BLANK_12") (pintype "bidirectional"))
    )
    (net (code "63") (name "unconnected-(Q6-EN-Pad10)") (class "Default")
      (node (ref "Q6") (pin "10") (pinfunction "EN_10") (pintype "bidirectional"))
    )
    (net (code "64") (name "unconnected-(Q6-EXTMODE-Pad15)") (class "Default")
      (node (ref "Q6") (pin "15") (pinfunction "EXTMODE_15") (pintype "bidirectional"))
    )
    (net (code "65") (name "unconnected-(Q6-OUTA-Pad16)") (class "Default")
      (node (ref "Q6") (pin "16") (pinfunction "OUTA_16") (pintype "bidirectional"))
    )
    (net (code "66") (name "unconnected-(Q6-PFD1-Pad13)") (class "Default")
      (node (ref "Q6") (pin "13") (pinfunction "PFD1_13") (pintype "bidirectional"))
    )
    (net (code "67") (name "unconnected-(Q6-PFD2-Pad11)") (class "Default")
      (node (ref "Q6") (pin "11") (pinfunction "PFD2_11") (pintype "bidirectional"))
    )
    (net (code "68") (name "unconnected-(Q6-PHASE-Pad3)") (class "Default")
      (node (ref "Q6") (pin "3") (pinfunction "PHASE_3") (pintype "bidirectional"))
    )
    (net (code "69") (name "unconnected-(Q8-A-Pad12)") (class "Default")
      (node (ref "Q8") (pin "12") (pinfunction "A_12") (pintype "bidirectional"))
    )
    (net (code "70") (name "unconnected-(Q8-B-Pad11)") (class "Default")
      (node (ref "Q8") (pin "11") (pinfunction "B_11") (pintype "bidirectional"))
    )
    (net (code "71") (name "unconnected-(Q8-CNT_EN-Pad13)") (class "Default")
      (node (ref "Q8") (pin "13") (pinfunction "CNT_EN_13") (pintype "bidirectional"))
    )
    (net (code "72") (name "unconnected-(Q8-DFLAG-Pad9)") (class "Default")
      (node (ref "Q8") (pin "9") (pinfunction "DFLAG_9") (pintype "bidirectional"))
    )
    (net (code "73") (name "unconnected-(Q8-INDEX-Pad10)") (class "Default")
      (node (ref "Q8") (pin "10") (pinfunction "INDEX_10") (pintype "bidirectional"))
    )
    (net (code "74") (name "unconnected-(Q8-LFLAG-Pad8)") (class "Default")
      (node (ref "Q8") (pin "8") (pinfunction "LFLAG_8") (pintype "bidirectional"))
    )
    (net (code "75") (name "unconnected-(Q8-MISO-Pad6)") (class "Default")
      (node (ref "Q8") (pin "6") (pinfunction "MISO_6") (pintype "bidirectional"))
    )
    (net (code "76") (name "unconnected-(Q8-MOSI-Pad7)") (class "Default")
      (node (ref "Q8") (pin "7") (pinfunction "MOSI_7") (pintype "bidirectional"))
    )
    (net (code "77") (name "unconnected-(Q8-SCK-Pad5)") (class "Default")
      (node (ref "Q8") (pin "5") (pinfunction "SCK_5") (pintype "bidirectional"))
    )
    (net (code "78") (name "unconnected-(Q8-SS{slash}-Pad4)") (class "Default")
      (node (ref "Q8") (pin "4") (pinfunction "SS/_4") (pintype "bidirectional"))
    )
    (net (code "79") (name "unconnected-(Q9-A-Pad12)") (class "Default")
      (node (ref "Q9") (pin "12") (pinfunction "A_12") (pintype "bidirectional"))
    )
    (net (code "80") (name "unconnected-(Q9-B-Pad11)") (class "Default")
      (node (ref "Q9") (pin "11") (pinfunction "B_11") (pintype "bidirectional"))
    )
    (net (code "81") (name "unconnected-(Q9-CNT_EN-Pad13)") (class "Default")
      (node (ref "Q9") (pin "13") (pinfunction "CNT_EN_13") (pintype "bidirectional"))
    )
    (net (code "82") (name "unconnected-(Q9-DFLAG-Pad9)") (class "Default")
      (node (ref "Q9") (pin "9") (pinfunction "DFLAG_9") (pintype "bidirectional"))
    )
    (net (code "83") (name "unconnected-(Q9-INDEX-Pad10)") (class "Default")
      (node (ref "Q9") (pin "10") (pinfunction "INDEX_10") (pintype "bidirectional"))
    )
    (net (code "84") (name "unconnected-(Q9-LFLAG-Pad8)") (class "Default")
      (node (ref "Q9") (pin "8") (pinfunction "LFLAG_8") (pintype "bidirectional"))
    )
    (net (code "85") (name "unconnected-(Q9-MISO-Pad6)") (class "Default")
      (node (ref "Q9") (pin "6") (pinfunction "MISO_6") (pintype "bidirectional"))
    )
    (net (code "86") (name "unconnected-(Q9-MOSI-Pad7)") (class "Default")
      (node (ref "Q9") (pin "7") (pinfunction "MOSI_7") (pintype "bidirectional"))
    )
    (net (code "87") (name "unconnected-(Q9-SCK-Pad5)") (class "Default")
      (node (ref "Q9") (pin "5") (pinfunction "SCK_5") (pintype "bidirectional"))
    )
    (net (code "88") (name "unconnected-(Q9-SS{slash}-Pad4)") (class "Default")
      (node (ref "Q9") (pin "4") (pinfunction "SS/_4") (pintype "bidirectional"))
    )
    (net (code "89") (name "unconnected-(R13-Pad1)") (class "Default")
      (node (ref "R13") (pin "1") (pinfunction "1_1") (pintype "passive"))
    )
    (net (code "90") (name "unconnected-(R15-Pad2)") (class "Default")
      (node (ref "R15") (pin "2") (pinfunction "2_2") (pintype "passive"))
    )
    (net (code "91") (name "unconnected-(R18-Pad1)") (class "Default")
      (node (ref "R18") (pin "1") (pinfunction "1_1") (pintype "passive"))
    )
    (net (code "92") (name "unconnected-(R20-Pad2)") (class "Default")
      (node (ref "R20") (pin "2") (pinfunction "2_2") (pintype "passive"))
    )
  )
)
